# SCH_HackerCard_2024-08-28.net
KiCad netlist of a schematic drawn in EasyEDA
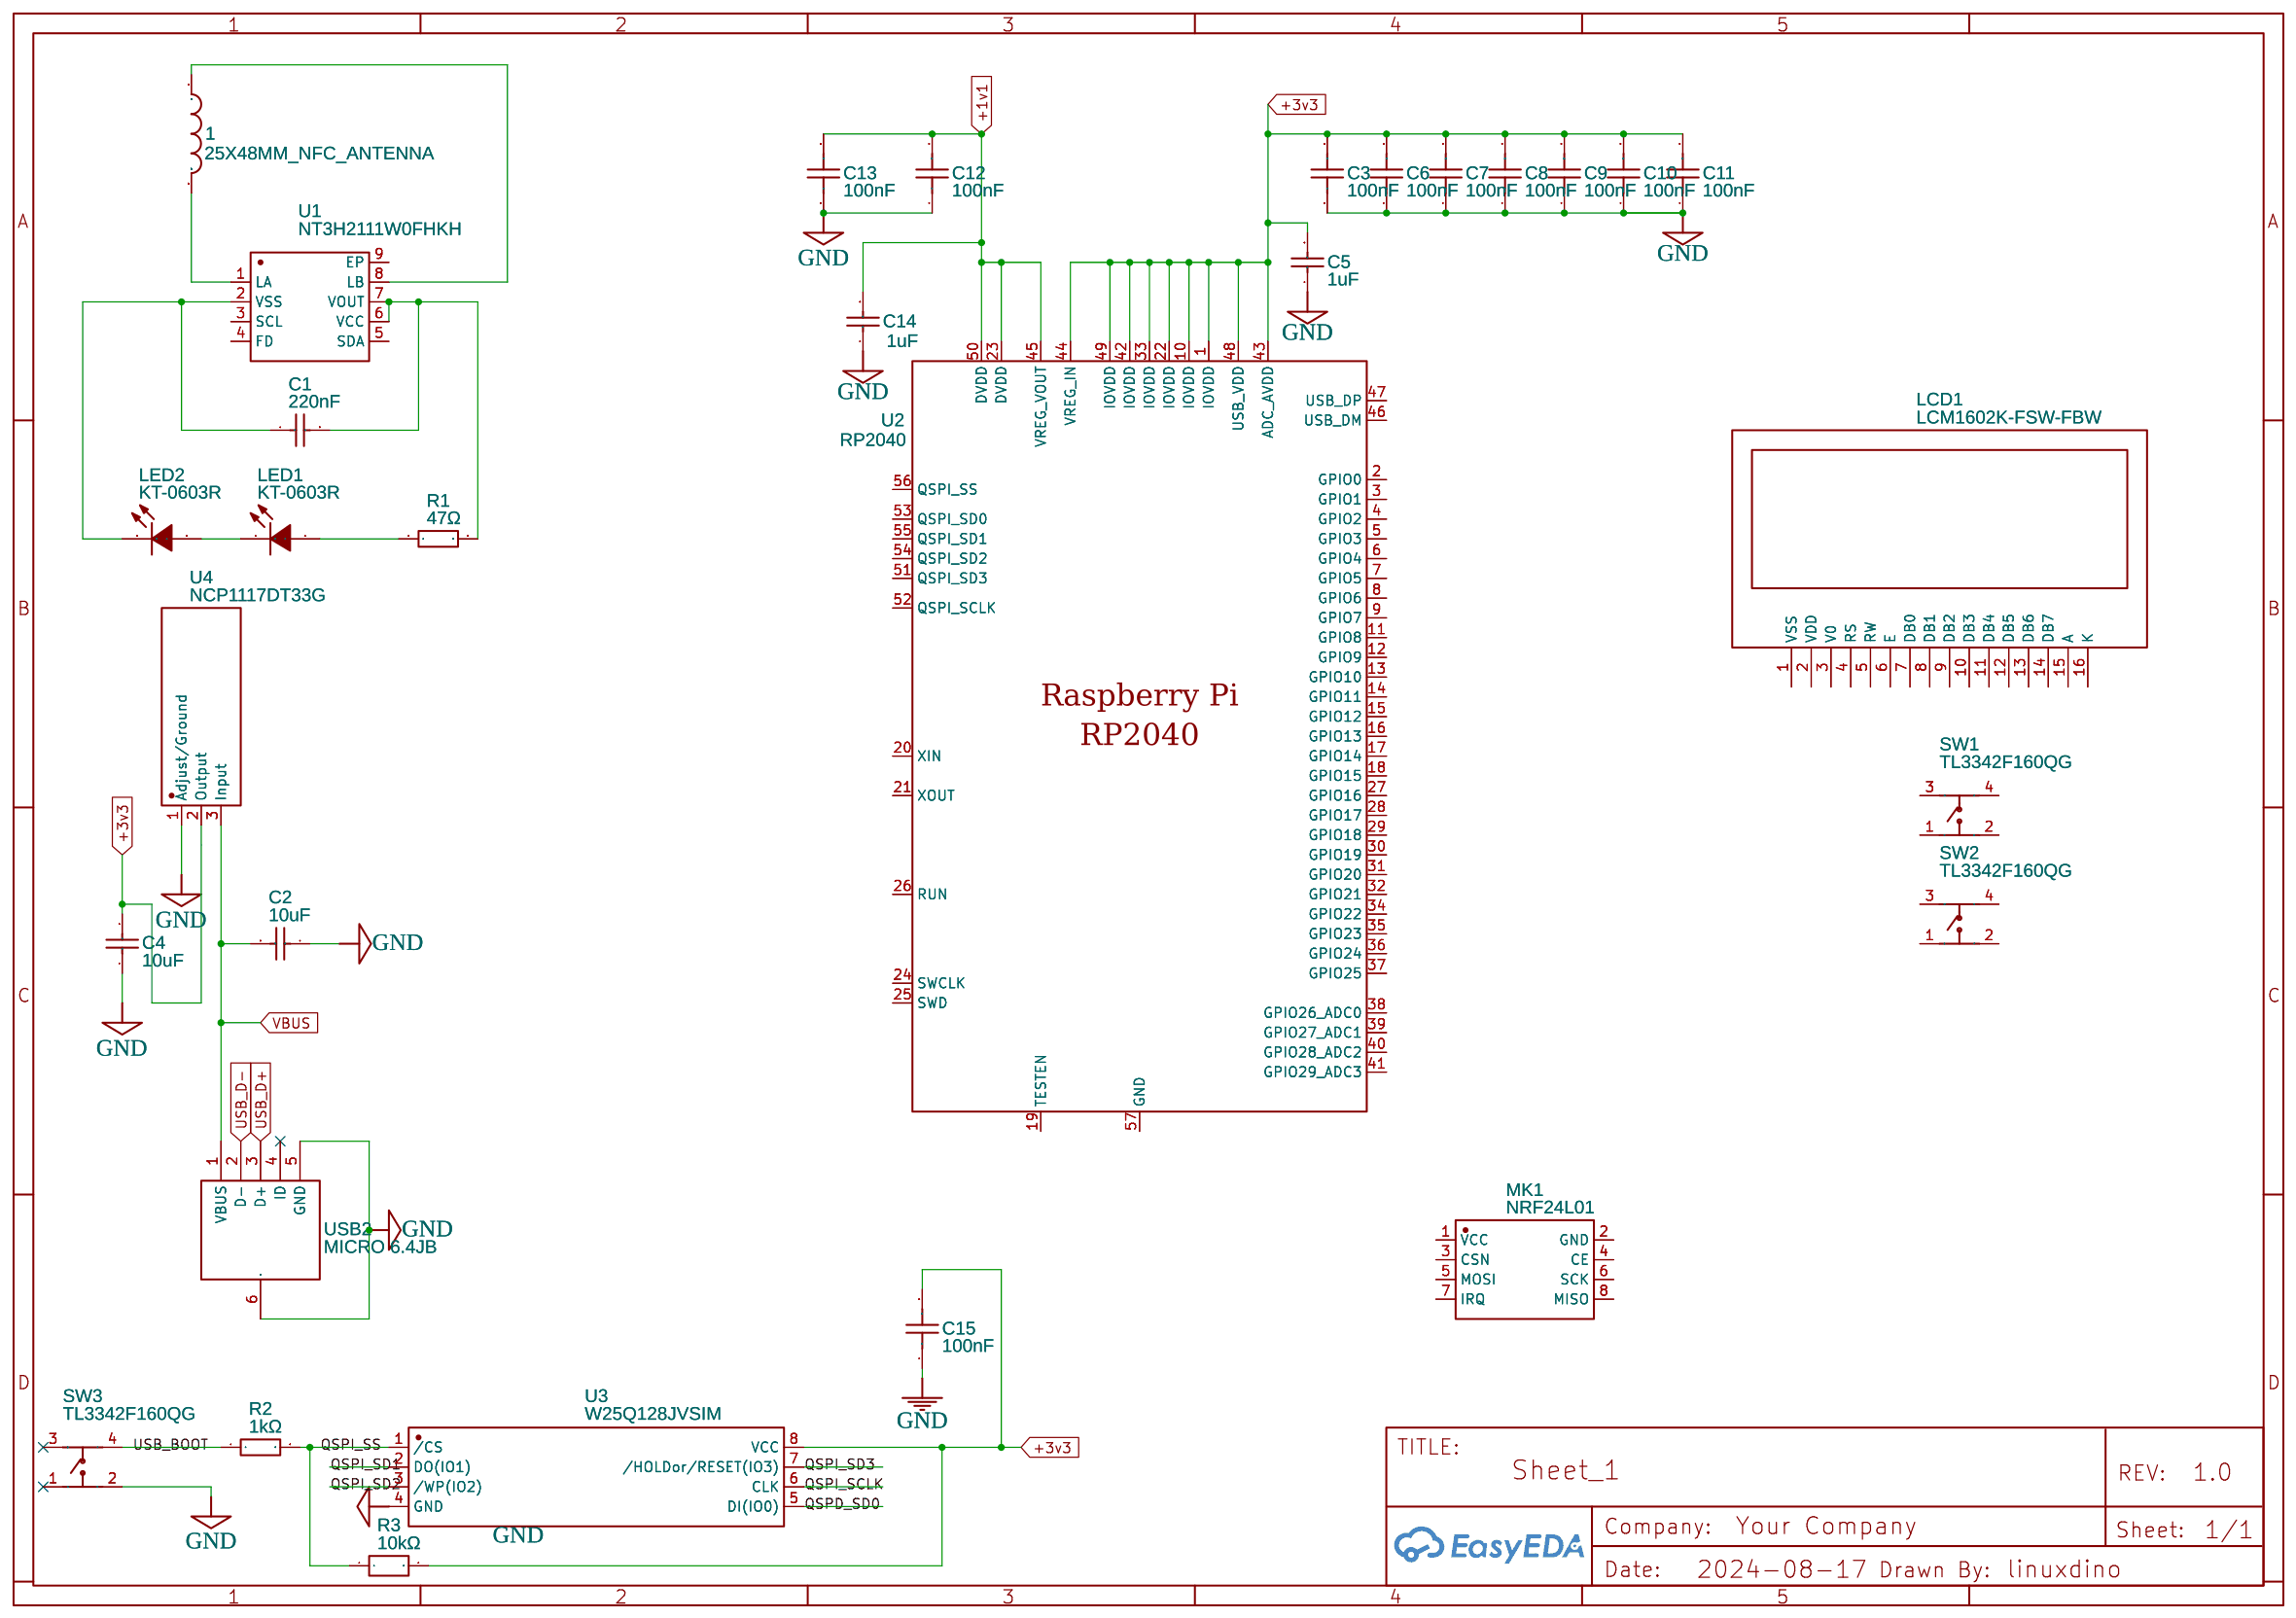
[diagram p0: schematic sheet]

(export (version "E")
  (design (tool "Eeschema 10.0.6"))
  (components
    (comp (ref "1") (value "25X48MM_NFC_ANTENNA") (libsource (lib "") (part "25X48MM_NFC_ANTENNA")))
    (comp (ref "C1")
      (value "220nF")
      (fields
        (field (name "Manufacturer Part") "CL10B224KA8NNNC")
        (field (name "Manufacturer") "SAMSUNG(三星)")
      )
      (libsource (lib "") (part "CL10B224KA8NNNC"))
    )
    (comp (ref "C2")
      (value "10uF")
      (fields
        (field (name "Manufacturer Part") "CL31A106KOHNNNE")
        (field (name "Manufacturer") "SAMSUNG(三星)")
      )
      (libsource (lib "") (part "CL31A106KOHNNNE_1"))
    )
    (comp (ref "C3")
      (value "100nF")
      (fields
        (field (name "Manufacturer Part") "CL10B104KB8NNNC")
        (field (name "Manufacturer") "SAMSUNG(三星)")
      )
      (libsource (lib "") (part "CL10B104KB8NNNC"))
    )
    (comp (ref "C4")
      (value "10uF")
      (fields
        (field (name "Manufacturer Part") "CL31A106KOHNNNE")
        (field (name "Manufacturer") "SAMSUNG(三星)")
      )
      (libsource (lib "") (part "CL31A106KOHNNNE"))
    )
    (comp (ref "C5")
      (value "1uF")
      (fields
        (field (name "Manufacturer Part") "CL10A105KO8NNNC")
        (field (name "Manufacturer") "SAMSUNG(三星)")
      )
      (libsource (lib "") (part "CL10A105KO8NNNC"))
    )
    (comp (ref "C6")
      (value "100nF")
      (fields
        (field (name "Manufacturer Part") "CL10B104KB8NNNC")
        (field (name "Manufacturer") "SAMSUNG(三星)")
      )
      (libsource (lib "") (part "CL10B104KB8NNNC"))
    )
    (comp (ref "C7")
      (value "100nF")
      (fields
        (field (name "Manufacturer Part") "CL10B104KB8NNNC")
        (field (name "Manufacturer") "SAMSUNG(三星)")
      )
      (libsource (lib "") (part "CL10B104KB8NNNC"))
    )
    (comp (ref "C8")
      (value "100nF")
      (fields
        (field (name "Manufacturer Part") "CL10B104KB8NNNC")
        (field (name "Manufacturer") "SAMSUNG(三星)")
      )
      (libsource (lib "") (part "CL10B104KB8NNNC"))
    )
    (comp (ref "C9")
      (value "100nF")
      (fields
        (field (name "Manufacturer Part") "CL10B104KB8NNNC")
        (field (name "Manufacturer") "SAMSUNG(三星)")
      )
      (libsource (lib "") (part "CL10B104KB8NNNC"))
    )
    (comp (ref "C10")
      (value "100nF")
      (fields
        (field (name "Manufacturer Part") "CL10B104KB8NNNC")
        (field (name "Manufacturer") "SAMSUNG(三星)")
      )
      (libsource (lib "") (part "CL10B104KB8NNNC"))
    )
    (comp (ref "C11")
      (value "100nF")
      (fields
        (field (name "Manufacturer Part") "CL10B104KB8NNNC")
        (field (name "Manufacturer") "SAMSUNG(三星)")
      )
      (libsource (lib "") (part "CL10B104KB8NNNC"))
    )
    (comp (ref "C12")
      (value "100nF")
      (fields
        (field (name "Manufacturer Part") "CL10B104KB8NNNC")
        (field (name "Manufacturer") "SAMSUNG(三星)")
      )
      (libsource (lib "") (part "CL10B104KB8NNNC"))
    )
    (comp (ref "C13")
      (value "100nF")
      (fields
        (field (name "Manufacturer Part") "CL10B104KB8NNNC")
        (field (name "Manufacturer") "SAMSUNG(三星)")
      )
      (libsource (lib "") (part "CL10B104KB8NNNC"))
    )
    (comp (ref "C14")
      (value "1uF")
      (fields
        (field (name "Manufacturer Part") "CL10A105KO8NNNC")
        (field (name "Manufacturer") "SAMSUNG(三星)")
      )
      (libsource (lib "") (part "CL10A105KO8NNNC"))
    )
    (comp (ref "C15")
      (value "100nF")
      (fields
        (field (name "Manufacturer Part") "CL10B104KB8NNNC")
        (field (name "Manufacturer") "SAMSUNG(三星)")
      )
      (libsource (lib "") (part "CL10B104KB8NNNC"))
    )
    (comp (ref "LCD1")
      (value "LCM1602K-FSW-FBW")
      (fields (field (name "Manufacturer") "LONTECH(厦门龙特)"))
      (libsource (lib "") (part "LCM1602K-FSW-FBW"))
    )
    (comp (ref "LED1")
      (value "KT-0603R")
      (fields (field (name "Manufacturer") "KENTO"))
      (libsource (lib "") (part "KT-0603R"))
    )
    (comp (ref "LED2")
      (value "KT-0603R")
      (fields (field (name "Manufacturer") "KENTO"))
      (libsource (lib "") (part "KT-0603R"))
    )
    (comp (ref "MK1")
      (value "NRF24L01")
      (fields (field (name "Manufacturer Part") "NF-04") (field (name "Manufacturer") "Ai-Thinker(安信可)"))
      (libsource (lib "") (part "NRF24L01"))
    )
    (comp (ref "R1")
      (value "47Ω")
      (fields
        (field (name "Manufacturer Part") "0603WAF470JT5E")
        (field (name "Manufacturer") "UNI-ROYAL(厚声)")
      )
      (libsource (lib "") (part "0603WAF470JT5E"))
    )
    (comp (ref "R2")
      (value "1kΩ")
      (fields
        (field (name "Manufacturer Part") "0603WAF1001T5E")
        (field (name "Manufacturer") "UNI-ROYAL(厚声)")
      )
      (libsource (lib "") (part "0603WAF1001T5E"))
    )
    (comp (ref "R3")
      (value "10kΩ")
      (fields (field (name "Manufacturer Part") "CR-03JL7---10K") (field (name "Manufacturer") "Viking(光颉)"))
      (libsource (lib "") (part "CR-03JL7---10K"))
    )
    (comp (ref "SW1")
      (value "TL3342F160QG")
      (fields (field (name "Manufacturer") "E-Switch"))
      (libsource (lib "") (part "TL3342F160QG"))
    )
    (comp (ref "SW2")
      (value "TL3342F160QG")
      (fields (field (name "Manufacturer") "E-Switch"))
      (libsource (lib "") (part "TL3342F160QG"))
    )
    (comp (ref "SW3")
      (value "TL3342F160QG")
      (fields (field (name "Manufacturer") "E-Switch"))
      (libsource (lib "") (part "TL3342F160QG"))
    )
    (comp (ref "U1")
      (value "NT3H2111W0FHKH")
      (fields (field (name "Manufacturer") "NXP(恩智浦)"))
      (libsource (lib "") (part "NT3H2111W0FHKH"))
    )
    (comp (ref "U2")
      (value "RP2040")
      (fields (field (name "Manufacturer") "Raspberry Pi(树莓派)"))
      (libsource (lib "") (part "RP2040"))
    )
    (comp (ref "U3")
      (value "W25Q128JVSIM")
      (fields (field (name "Manufacturer") "WINBOND(华邦)"))
      (libsource (lib "") (part "W25Q128JVSIM"))
    )
    (comp (ref "U4")
      (value "NCP1117DT33G")
      (fields (field (name "Manufacturer") "onsemi(安森美)"))
      (libsource (lib "") (part "NCP1117DT33G"))
    )
    (comp (ref "USB2")
      (value "MICRO 6.4JB")
      (fields (field (name "Manufacturer") "SHOU HAN(首韩)"))
      (libsource (lib "") (part "MICRO 6.4JB"))
    )
  )
  (nets
    (net (code "1") (name "+1v1") (class "Default")
      (node (ref "C12") (pin "2") (pinfunction "2_2") (pintype "unspecified"))
      (node (ref "C13") (pin "2") (pinfunction "2_2") (pintype "unspecified"))
      (node (ref "C14") (pin "2") (pinfunction "2_2") (pintype "input"))
      (node (ref "U2") (pin "23") (pinfunction "DVDD_23") (pintype "bidirectional"))
      (node (ref "U2") (pin "45") (pinfunction "VREG_VOUT_45") (pintype "bidirectional"))
      (node (ref "U2") (pin "50") (pinfunction "DVDD_50") (pintype "bidirectional"))
    )
    (net (code "2") (name "+3v3") (class "Default")
      (node (ref "C10") (pin "2") (pinfunction "2_2") (pintype "unspecified"))
      (node (ref "C11") (pin "2") (pinfunction "2_2") (pintype "unspecified"))
      (node (ref "C15") (pin "2") (pinfunction "2_2") (pintype "unspecified"))
      (node (ref "C3") (pin "2") (pinfunction "2_2") (pintype "unspecified"))
      (node (ref "C4") (pin "2") (pinfunction "2_2") (pintype "input"))
      (node (ref "C5") (pin "2") (pinfunction "2_2") (pintype "input"))
      (node (ref "C6") (pin "2") (pinfunction "2_2") (pintype "unspecified"))
      (node (ref "C7") (pin "2") (pinfunction "2_2") (pintype "unspecified"))
      (node (ref "C8") (pin "2") (pinfunction "2_2") (pintype "unspecified"))
      (node (ref "C9") (pin "2") (pinfunction "2_2") (pintype "unspecified"))
      (node (ref "R3") (pin "2") (pinfunction "2_2") (pintype "unspecified"))
      (node (ref "U2") (pin "1") (pinfunction "IOVDD_1") (pintype "bidirectional"))
      (node (ref "U2") (pin "10") (pinfunction "IOVDD_10") (pintype "bidirectional"))
      (node (ref "U2") (pin "22") (pinfunction "IOVDD_22") (pintype "bidirectional"))
      (node (ref "U2") (pin "33") (pinfunction "IOVDD_33") (pintype "bidirectional"))
      (node (ref "U2") (pin "42") (pinfunction "IOVDD_42") (pintype "bidirectional"))
      (node (ref "U2") (pin "43") (pinfunction "ADC_AVDD_43") (pintype "bidirectional"))
      (node (ref "U2") (pin "44") (pinfunction "VREG_IN_44") (pintype "bidirectional"))
      (node (ref "U2") (pin "48") (pinfunction "USB_VDD_48") (pintype "bidirectional"))
      (node (ref "U2") (pin "49") (pinfunction "IOVDD_49") (pintype "bidirectional"))
      (node (ref "U3") (pin "8") (pinfunction "VCC_8") (pintype "unspecified"))
      (node (ref "U4") (pin "2") (pinfunction "Output_2") (pintype "unspecified"))
    )
    (net (code "3") (name "/QSPD_SD0") (class "Default")
      (node (ref "U3") (pin "5") (pinfunction "DI(IO0)_5") (pintype "unspecified"))
    )
    (net (code "4") (name "/QSPI_SCLK") (class "Default")
      (node (ref "U3") (pin "6") (pinfunction "CLK_6") (pintype "unspecified"))
    )
    (net (code "5") (name "/QSPI_SD1") (class "Default")
      (node (ref "U3") (pin "2") (pinfunction "DO(IO1)_2") (pintype "unspecified"))
    )
    (net (code "6") (name "/QSPI_SD2") (class "Default")
      (node (ref "U3") (pin "3") (pinfunction "/WP(IO2)_3") (pintype "unspecified"))
    )
    (net (code "7") (name "/QSPI_SD3") (class "Default")
      (node (ref "U3") (pin "7") (pinfunction "/HOLDor/RESET(IO3)_7") (pintype "unspecified"))
    )
    (net (code "8") (name "/QSPI_SS") (class "Default")
      (node (ref "R2") (pin "2") (pinfunction "2_2") (pintype "input"))
      (node (ref "R3") (pin "1") (pinfunction "1_1") (pintype "unspecified"))
      (node (ref "U3") (pin "1") (pinfunction "/CS_1") (pintype "unspecified"))
    )
    (net (code "9") (name "/USB_BOOT") (class "Default")
      (node (ref "R2") (pin "1") (pinfunction "1_1") (pintype "input"))
      (node (ref "SW3") (pin "4") (pinfunction "4_4") (pintype "unspecified"))
    )
    (net (code "10") (name "GND") (class "Default")
      (node (ref "C10") (pin "1") (pinfunction "1_1") (pintype "unspecified"))
      (node (ref "C11") (pin "1") (pinfunction "1_1") (pintype "unspecified"))
      (node (ref "C12") (pin "1") (pinfunction "1_1") (pintype "unspecified"))
      (node (ref "C13") (pin "1") (pinfunction "1_1") (pintype "unspecified"))
      (node (ref "C14") (pin "1") (pinfunction "1_1") (pintype "input"))
      (node (ref "C15") (pin "1") (pinfunction "1_1") (pintype "unspecified"))
      (node (ref "C2") (pin "1") (pinfunction "1_1") (pintype "input"))
      (node (ref "C3") (pin "1") (pinfunction "1_1") (pintype "unspecified"))
      (node (ref "C4") (pin "1") (pinfunction "1_1") (pintype "input"))
      (node (ref "C5") (pin "1") (pinfunction "1_1") (pintype "input"))
      (node (ref "C6") (pin "1") (pinfunction "1_1") (pintype "unspecified"))
      (node (ref "C7") (pin "1") (pinfunction "1_1") (pintype "unspecified"))
      (node (ref "C8") (pin "1") (pinfunction "1_1") (pintype "unspecified"))
      (node (ref "C9") (pin "1") (pinfunction "1_1") (pintype "unspecified"))
      (node (ref "SW3") (pin "2") (pinfunction "2_2") (pintype "unspecified"))
      (node (ref "U3") (pin "4") (pinfunction "GND_4") (pintype "unspecified"))
      (node (ref "U4") (pin "1") (pinfunction "Adjust/Ground_1") (pintype "unspecified"))
      (node (ref "USB2") (pin "5") (pinfunction "GND_5") (pintype "input"))
      (node (ref "USB2") (pin "6") (pinfunction "EH_6") (pintype "input"))
    )
    (net (code "11") (name "Net-(LED1-A)") (class "Default")
      (node (ref "LED1") (pin "2") (pinfunction "A_2") (pintype "unspecified"))
      (node (ref "R1") (pin "1") (pinfunction "1_1") (pintype "input"))
    )
    (net (code "12") (name "Net-(LED1-K)") (class "Default")
      (node (ref "LED1") (pin "1") (pinfunction "K_1") (pintype "unspecified"))
      (node (ref "LED2") (pin "2") (pinfunction "A_2") (pintype "unspecified"))
    )
    (net (code "13") (name "Net-(LED2-K)") (class "Default")
      (node (ref "C1") (pin "1") (pinfunction "1_1") (pintype "input"))
      (node (ref "LED2") (pin "1") (pinfunction "K_1") (pintype "unspecified"))
      (node (ref "U1") (pin "2") (pinfunction "VSS_2") (pintype "unspecified"))
    )
    (net (code "14") (name "Net-(U1-LA)") (class "Default")
      (node (ref "1") (pin "P$2") (pinfunction "P$2_P$2") (pintype "bidirectional"))
      (node (ref "U1") (pin "1") (pinfunction "LA_1") (pintype "unspecified"))
    )
    (net (code "15") (name "Net-(U1-LB)") (class "Default")
      (node (ref "1") (pin "P$1") (pinfunction "P$1_P$1") (pintype "bidirectional"))
      (node (ref "U1") (pin "8") (pinfunction "LB_8") (pintype "unspecified"))
    )
    (net (code "16") (name "Net-(U1-VCC)") (class "Default")
      (node (ref "C1") (pin "2") (pinfunction "2_2") (pintype "input"))
      (node (ref "R1") (pin "2") (pinfunction "2_2") (pintype "input"))
      (node (ref "U1") (pin "6") (pinfunction "VCC_6") (pintype "unspecified"))
      (node (ref "U1") (pin "7") (pinfunction "VOUT_7") (pintype "unspecified"))
    )
    (net (code "17") (name "USB_D+") (class "Default")
      (node (ref "USB2") (pin "3") (pinfunction "D+_3") (pintype "input"))
    )
    (net (code "18") (name "USB_D-") (class "Default")
      (node (ref "USB2") (pin "2") (pinfunction "D-_2") (pintype "input"))
    )
    (net (code "19") (name "VBUS") (class "Default")
      (node (ref "C2") (pin "2") (pinfunction "2_2") (pintype "input"))
      (node (ref "U4") (pin "3") (pinfunction "Input_3") (pintype "unspecified"))
      (node (ref "USB2") (pin "1") (pinfunction "VBUS_1") (pintype "input"))
    )
    (net (code "20") (name "unconnected-(LCD1-A-Pad15)") (class "Default")
      (node (ref "LCD1") (pin "15") (pinfunction "A_15") (pintype "unspecified"))
    )
    (net (code "21") (name "unconnected-(LCD1-DB0-Pad7)") (class "Default")
      (node (ref "LCD1") (pin "7") (pinfunction "DB0_7") (pintype "unspecified"))
    )
    (net (code "22") (name "unconnected-(LCD1-DB1-Pad8)") (class "Default")
      (node (ref "LCD1") (pin "8") (pinfunction "DB1_8") (pintype "unspecified"))
    )
    (net (code "23") (name "unconnected-(LCD1-DB2-Pad9)") (class "Default")
      (node (ref "LCD1") (pin "9") (pinfunction "DB2_9") (pintype "unspecified"))
    )
    (net (code "24") (name "unconnected-(LCD1-DB3-Pad10)") (class "Default")
      (node (ref "LCD1") (pin "10") (pinfunction "DB3_10") (pintype "unspecified"))
    )
    (net (code "25") (name "unconnected-(LCD1-DB4-Pad11)") (class "Default")
      (node (ref "LCD1") (pin "11") (pinfunction "DB4_11") (pintype "unspecified"))
    )
    (net (code "26") (name "unconnected-(LCD1-DB5-Pad12)") (class "Default")
      (node (ref "LCD1") (pin "12") (pinfunction "DB5_12") (pintype "unspecified"))
    )
    (net (code "27") (name "unconnected-(LCD1-DB6-Pad13)") (class "Default")
      (node (ref "LCD1") (pin "13") (pinfunction "DB6_13") (pintype "unspecified"))
    )
    (net (code "28") (name "unconnected-(LCD1-DB7-Pad14)") (class "Default")
      (node (ref "LCD1") (pin "14") (pinfunction "DB7_14") (pintype "unspecified"))
    )
    (net (code "29") (name "unconnected-(LCD1-E-Pad6)") (class "Default")
      (node (ref "LCD1") (pin "6") (pinfunction "E_6") (pintype "unspecified"))
    )
    (net (code "30") (name "unconnected-(LCD1-K-Pad16)") (class "Default")
      (node (ref "LCD1") (pin "16") (pinfunction "K_16") (pintype "unspecified"))
    )
    (net (code "31") (name "unconnected-(LCD1-RS-Pad4)") (class "Default")
      (node (ref "LCD1") (pin "4") (pinfunction "RS_4") (pintype "unspecified"))
    )
    (net (code "32") (name "unconnected-(LCD1-RW-Pad5)") (class "Default")
      (node (ref "LCD1") (pin "5") (pinfunction "RW_5") (pintype "unspecified"))
    )
    (net (code "33") (name "unconnected-(LCD1-V0-Pad3)") (class "Default")
      (node (ref "LCD1") (pin "3") (pinfunction "V0_3") (pintype "unspecified"))
    )
    (net (code "34") (name "unconnected-(LCD1-VDD-Pad2)") (class "Default")
      (node (ref "LCD1") (pin "2") (pinfunction "VDD_2") (pintype "unspecified"))
    )
    (net (code "35") (name "unconnected-(LCD1-VSS-Pad1)") (class "Default")
      (node (ref "LCD1") (pin "1") (pinfunction "VSS_1") (pintype "unspecified"))
    )
    (net (code "36") (name "unconnected-(MK1-CE-Pad4)") (class "Default")
      (node (ref "MK1") (pin "4") (pinfunction "CE_4") (pintype "unspecified"))
    )
    (net (code "37") (name "unconnected-(MK1-CSN-Pad3)") (class "Default")
      (node (ref "MK1") (pin "3") (pinfunction "CSN_3") (pintype "unspecified"))
    )
    (net (code "38") (name "unconnected-(MK1-GND-Pad2)") (class "Default")
      (node (ref "MK1") (pin "2") (pinfunction "GND_2") (pintype "unspecified"))
    )
    (net (code "39") (name "unconnected-(MK1-IRQ-Pad7)") (class "Default")
      (node (ref "MK1") (pin "7") (pinfunction "IRQ_7") (pintype "unspecified"))
    )
    (net (code "40") (name "unconnected-(MK1-MISO-Pad8)") (class "Default")
      (node (ref "MK1") (pin "8") (pinfunction "MISO_8") (pintype "unspecified"))
    )
    (net (code "41") (name "unconnected-(MK1-MOSI-Pad5)") (class "Default")
      (node (ref "MK1") (pin "5") (pinfunction "MOSI_5") (pintype "unspecified"))
    )
    (net (code "42") (name "unconnected-(MK1-SCK-Pad6)") (class "Default")
      (node (ref "MK1") (pin "6") (pinfunction "SCK_6") (pintype "unspecified"))
    )
    (net (code "43") (name "unconnected-(MK1-VCC-Pad1)") (class "Default")
      (node (ref "MK1") (pin "1") (pinfunction "VCC_1") (pintype "unspecified"))
    )
    (net (code "44") (name "unconnected-(SW1-Pad1)") (class "Default")
      (node (ref "SW1") (pin "1") (pinfunction "1_1") (pintype "unspecified"))
    )
    (net (code "45") (name "unconnected-(SW1-Pad2)") (class "Default")
      (node (ref "SW1") (pin "2") (pinfunction "2_2") (pintype "unspecified"))
    )
    (net (code "46") (name "unconnected-(SW1-Pad3)") (class "Default")
      (node (ref "SW1") (pin "3") (pinfunction "3_3") (pintype "unspecified"))
    )
    (net (code "47") (name "unconnected-(SW1-Pad4)") (class "Default")
      (node (ref "SW1") (pin "4") (pinfunction "4_4") (pintype "unspecified"))
    )
    (net (code "48") (name "unconnected-(SW2-Pad1)") (class "Default")
      (node (ref "SW2") (pin "1") (pinfunction "1_1") (pintype "unspecified"))
    )
    (net (code "49") (name "unconnected-(SW2-Pad2)") (class "Default")
      (node (ref "SW2") (pin "2") (pinfunction "2_2") (pintype "unspecified"))
    )
    (net (code "50") (name "unconnected-(SW2-Pad3)") (class "Default")
      (node (ref "SW2") (pin "3") (pinfunction "3_3") (pintype "unspecified"))
    )
    (net (code "51") (name "unconnected-(SW2-Pad4)") (class "Default")
      (node (ref "SW2") (pin "4") (pinfunction "4_4") (pintype "unspecified"))
    )
    (net (code "52") (name "unconnected-(SW3-Pad1)") (class "Default")
      (node (ref "SW3") (pin "1") (pinfunction "1_1") (pintype "unspecified+no_connect"))
    )
    (net (code "53") (name "unconnected-(SW3-Pad3)") (class "Default")
      (node (ref "SW3") (pin "3") (pinfunction "3_3") (pintype "unspecified+no_connect"))
    )
    (net (code "54") (name "unconnected-(U1-EP-Pad9)") (class "Default")
      (node (ref "U1") (pin "9") (pinfunction "EP_9") (pintype "unspecified"))
    )
    (net (code "55") (name "unconnected-(U1-FD-Pad4)") (class "Default")
      (node (ref "U1") (pin "4") (pinfunction "FD_4") (pintype "unspecified"))
    )
    (net (code "56") (name "unconnected-(U1-SCL-Pad3)") (class "Default")
      (node (ref "U1") (pin "3") (pinfunction "SCL_3") (pintype "unspecified"))
    )
    (net (code "57") (name "unconnected-(U1-SDA-Pad5)") (class "Default")
      (node (ref "U1") (pin "5") (pinfunction "SDA_5") (pintype "unspecified"))
    )
    (net (code "58") (name "unconnected-(U2-GND-Pad57)") (class "Default")
      (node (ref "U2") (pin "57") (pinfunction "GND_57") (pintype "bidirectional"))
    )
    (net (code "59") (name "unconnected-(U2-GPIO0-Pad2)") (class "Default")
      (node (ref "U2") (pin "2") (pinfunction "GPIO0_2") (pintype "bidirectional"))
    )
    (net (code "60") (name "unconnected-(U2-GPIO1-Pad3)") (class "Default")
      (node (ref "U2") (pin "3") (pinfunction "GPIO1_3") (pintype "bidirectional"))
    )
    (net (code "61") (name "unconnected-(U2-GPIO2-Pad4)") (class "Default")
      (node (ref "U2") (pin "4") (pinfunction "GPIO2_4") (pintype "bidirectional"))
    )
    (net (code "62") (name "unconnected-(U2-GPIO3-Pad5)") (class "Default")
      (node (ref "U2") (pin "5") (pinfunction "GPIO3_5") (pintype "bidirectional"))
    )
    (net (code "63") (name "unconnected-(U2-GPIO4-Pad6)") (class "Default")
      (node (ref "U2") (pin "6") (pinfunction "GPIO4_6") (pintype "bidirectional"))
    )
    (net (code "64") (name "unconnected-(U2-GPIO5-Pad7)") (class "Default")
      (node (ref "U2") (pin "7") (pinfunction "GPIO5_7") (pintype "bidirectional"))
    )
    (net (code "65") (name "unconnected-(U2-GPIO6-Pad8)") (class "Default")
      (node (ref "U2") (pin "8") (pinfunction "GPIO6_8") (pintype "bidirectional"))
    )
    (net (code "66") (name "unconnected-(U2-GPIO7-Pad9)") (class "Default")
      (node (ref "U2") (pin "9") (pinfunction "GPIO7_9") (pintype "bidirectional"))
    )
    (net (code "67") (name "unconnected-(U2-GPIO8-Pad11)") (class "Default")
      (node (ref "U2") (pin "11") (pinfunction "GPIO8_11") (pintype "bidirectional"))
    )
    (net (code "68") (name "unconnected-(U2-GPIO9-Pad12)") (class "Default")
      (node (ref "U2") (pin "12") (pinfunction "GPIO9_12") (pintype "bidirectional"))
    )
    (net (code "69") (name "unconnected-(U2-GPIO10-Pad13)") (class "Default")
      (node (ref "U2") (pin "13") (pinfunction "GPIO10_13") (pintype "bidirectional"))
    )
    (net (code "70") (name "unconnected-(U2-GPIO11-Pad14)") (class "Default")
      (node (ref "U2") (pin "14") (pinfunction "GPIO11_14") (pintype "bidirectional"))
    )
    (net (code "71") (name "unconnected-(U2-GPIO12-Pad15)") (class "Default")
      (node (ref "U2") (pin "15") (pinfunction "GPIO12_15") (pintype "bidirectional"))
    )
    (net (code "72") (name "unconnected-(U2-GPIO13-Pad16)") (class "Default")
      (node (ref "U2") (pin "16") (pinfunction "GPIO13_16") (pintype "bidirectional"))
    )
    (net (code "73") (name "unconnected-(U2-GPIO14-Pad17)") (class "Default")
      (node (ref "U2") (pin "17") (pinfunction "GPIO14_17") (pintype "bidirectional"))
    )
    (net (code "74") (name "unconnected-(U2-GPIO15-Pad18)") (class "Default")
      (node (ref "U2") (pin "18") (pinfunction "GPIO15_18") (pintype "bidirectional"))
    )
    (net (code "75") (name "unconnected-(U2-GPIO16-Pad27)") (class "Default")
      (node (ref "U2") (pin "27") (pinfunction "GPIO16_27") (pintype "bidirectional"))
    )
    (net (code "76") (name "unconnected-(U2-GPIO17-Pad28)") (class "Default")
      (node (ref "U2") (pin "28") (pinfunction "GPIO17_28") (pintype "bidirectional"))
    )
    (net (code "77") (name "unconnected-(U2-GPIO18-Pad29)") (class "Default")
      (node (ref "U2") (pin "29") (pinfunction "GPIO18_29") (pintype "bidirectional"))
    )
    (net (code "78") (name "unconnected-(U2-GPIO19-Pad30)") (class "Default")
      (node (ref "U2") (pin "30") (pinfunction "GPIO19_30") (pintype "bidirectional"))
    )
    (net (code "79") (name "unconnected-(U2-GPIO20-Pad31)") (class "Default")
      (node (ref "U2") (pin "31") (pinfunction "GPIO20_31") (pintype "bidirectional"))
    )
    (net (code "80") (name "unconnected-(U2-GPIO21-Pad32)") (class "Default")
      (node (ref "U2") (pin "32") (pinfunction "GPIO21_32") (pintype "bidirectional"))
    )
    (net (code "81") (name "unconnected-(U2-GPIO22-Pad34)") (class "Default")
      (node (ref "U2") (pin "34") (pinfunction "GPIO22_34") (pintype "bidirectional"))
    )
    (net (code "82") (name "unconnected-(U2-GPIO23-Pad35)") (class "Default")
      (node (ref "U2") (pin "35") (pinfunction "GPIO23_35") (pintype "bidirectional"))
    )
    (net (code "83") (name "unconnected-(U2-GPIO24-Pad36)") (class "Default")
      (node (ref "U2") (pin "36") (pinfunction "GPIO24_36") (pintype "bidirectional"))
    )
    (net (code "84") (name "unconnected-(U2-GPIO25-Pad37)") (class "Default")
      (node (ref "U2") (pin "37") (pinfunction "GPIO25_37") (pintype "bidirectional"))
    )
    (net (code "85") (name "unconnected-(U2-GPIO26_ADC0-Pad38)") (class "Default")
      (node (ref "U2") (pin "38") (pinfunction "GPIO26_ADC0_38") (pintype "bidirectional"))
    )
    (net (code "86") (name "unconnected-(U2-GPIO27_ADC1-Pad39)") (class "Default")
      (node (ref "U2") (pin "39") (pinfunction "GPIO27_ADC1_39") (pintype "bidirectional"))
    )
    (net (code "87") (name "unconnected-(U2-GPIO28_ADC2-Pad40)") (class "Default")
      (node (ref "U2") (pin "40") (pinfunction "GPIO28_ADC2_40") (pintype "bidirectional"))
    )
    (net (code "88") (name "unconnected-(U2-GPIO29_ADC3-Pad41)") (class "Default")
      (node (ref "U2") (pin "41") (pinfunction "GPIO29_ADC3_41") (pintype "bidirectional"))
    )
    (net (code "89") (name "unconnected-(U2-QSPI_SCLK-Pad52)") (class "Default")
      (node (ref "U2") (pin "52") (pinfunction "QSPI_SCLK_52") (pintype "output"))
    )
    (net (code "90") (name "unconnected-(U2-QSPI_SD0-Pad53)") (class "Default")
      (node (ref "U2") (pin "53") (pinfunction "QSPI_SD0_53") (pintype "bidirectional"))
    )
    (net (code "91") (name "unconnected-(U2-QSPI_SD1-Pad55)") (class "Default")
      (node (ref "U2") (pin "55") (pinfunction "QSPI_SD1_55") (pintype "bidirectional"))
    )
    (net (code "92") (name "unconnected-(U2-QSPI_SD2-Pad54)") (class "Default")
      (node (ref "U2") (pin "54") (pinfunction "QSPI_SD2_54") (pintype "bidirectional"))
    )
    (net (code "93") (name "unconnected-(U2-QSPI_SD3-Pad51)") (class "Default")
      (node (ref "U2") (pin "51") (pinfunction "QSPI_SD3_51") (pintype "bidirectional"))
    )
    (net (code "94") (name "unconnected-(U2-QSPI_SS-Pad56)") (class "Default")
      (node (ref "U2") (pin "56") (pinfunction "QSPI_SS_56") (pintype "bidirectional"))
    )
    (net (code "95") (name "unconnected-(U2-RUN-Pad26)") (class "Default")
      (node (ref "U2") (pin "26") (pinfunction "RUN_26") (pintype "input"))
    )
    (net (code "96") (name "unconnected-(U2-SWCLK-Pad24)") (class "Default")
      (node (ref "U2") (pin "24") (pinfunction "SWCLK_24") (pintype "output"))
    )
    (net (code "97") (name "unconnected-(U2-SWD-Pad25)") (class "Default")
      (node (ref "U2") (pin "25") (pinfunction "SWD_25") (pintype "bidirectional"))
    )
    (net (code "98") (name "unconnected-(U2-TESTEN-Pad19)") (class "Default")
      (node (ref "U2") (pin "19") (pinfunction "TESTEN_19") (pintype "unspecified"))
    )
    (net (code "99") (name "unconnected-(U2-USB_DM-Pad46)") (class "Default")
      (node (ref "U2") (pin "46") (pinfunction "USB_DM_46") (pintype "bidirectional"))
    )
    (net (code "100") (name "unconnected-(U2-USB_DP-Pad47)") (class "Default")
      (node (ref "U2") (pin "47") (pinfunction "USB_DP_47") (pintype "bidirectional"))
    )
    (net (code "101") (name "unconnected-(U2-XIN-Pad20)") (class "Default")
      (node (ref "U2") (pin "20") (pinfunction "XIN_20") (pintype "input"))
    )
    (net (code "102") (name "unconnected-(U2-XOUT-Pad21)") (class "Default")
      (node (ref "U2") (pin "21") (pinfunction "XOUT_21") (pintype "unspecified"))
    )
    (net (code "103") (name "unconnected-(USB2-ID-Pad4)") (class "Default")
      (node (ref "USB2") (pin "4") (pinfunction "ID_4") (pintype "input+no_connect"))
    )
  )
)
